# SuperTiny-REV4.net
KiCad netlist of a schematic drawn in EAGLE
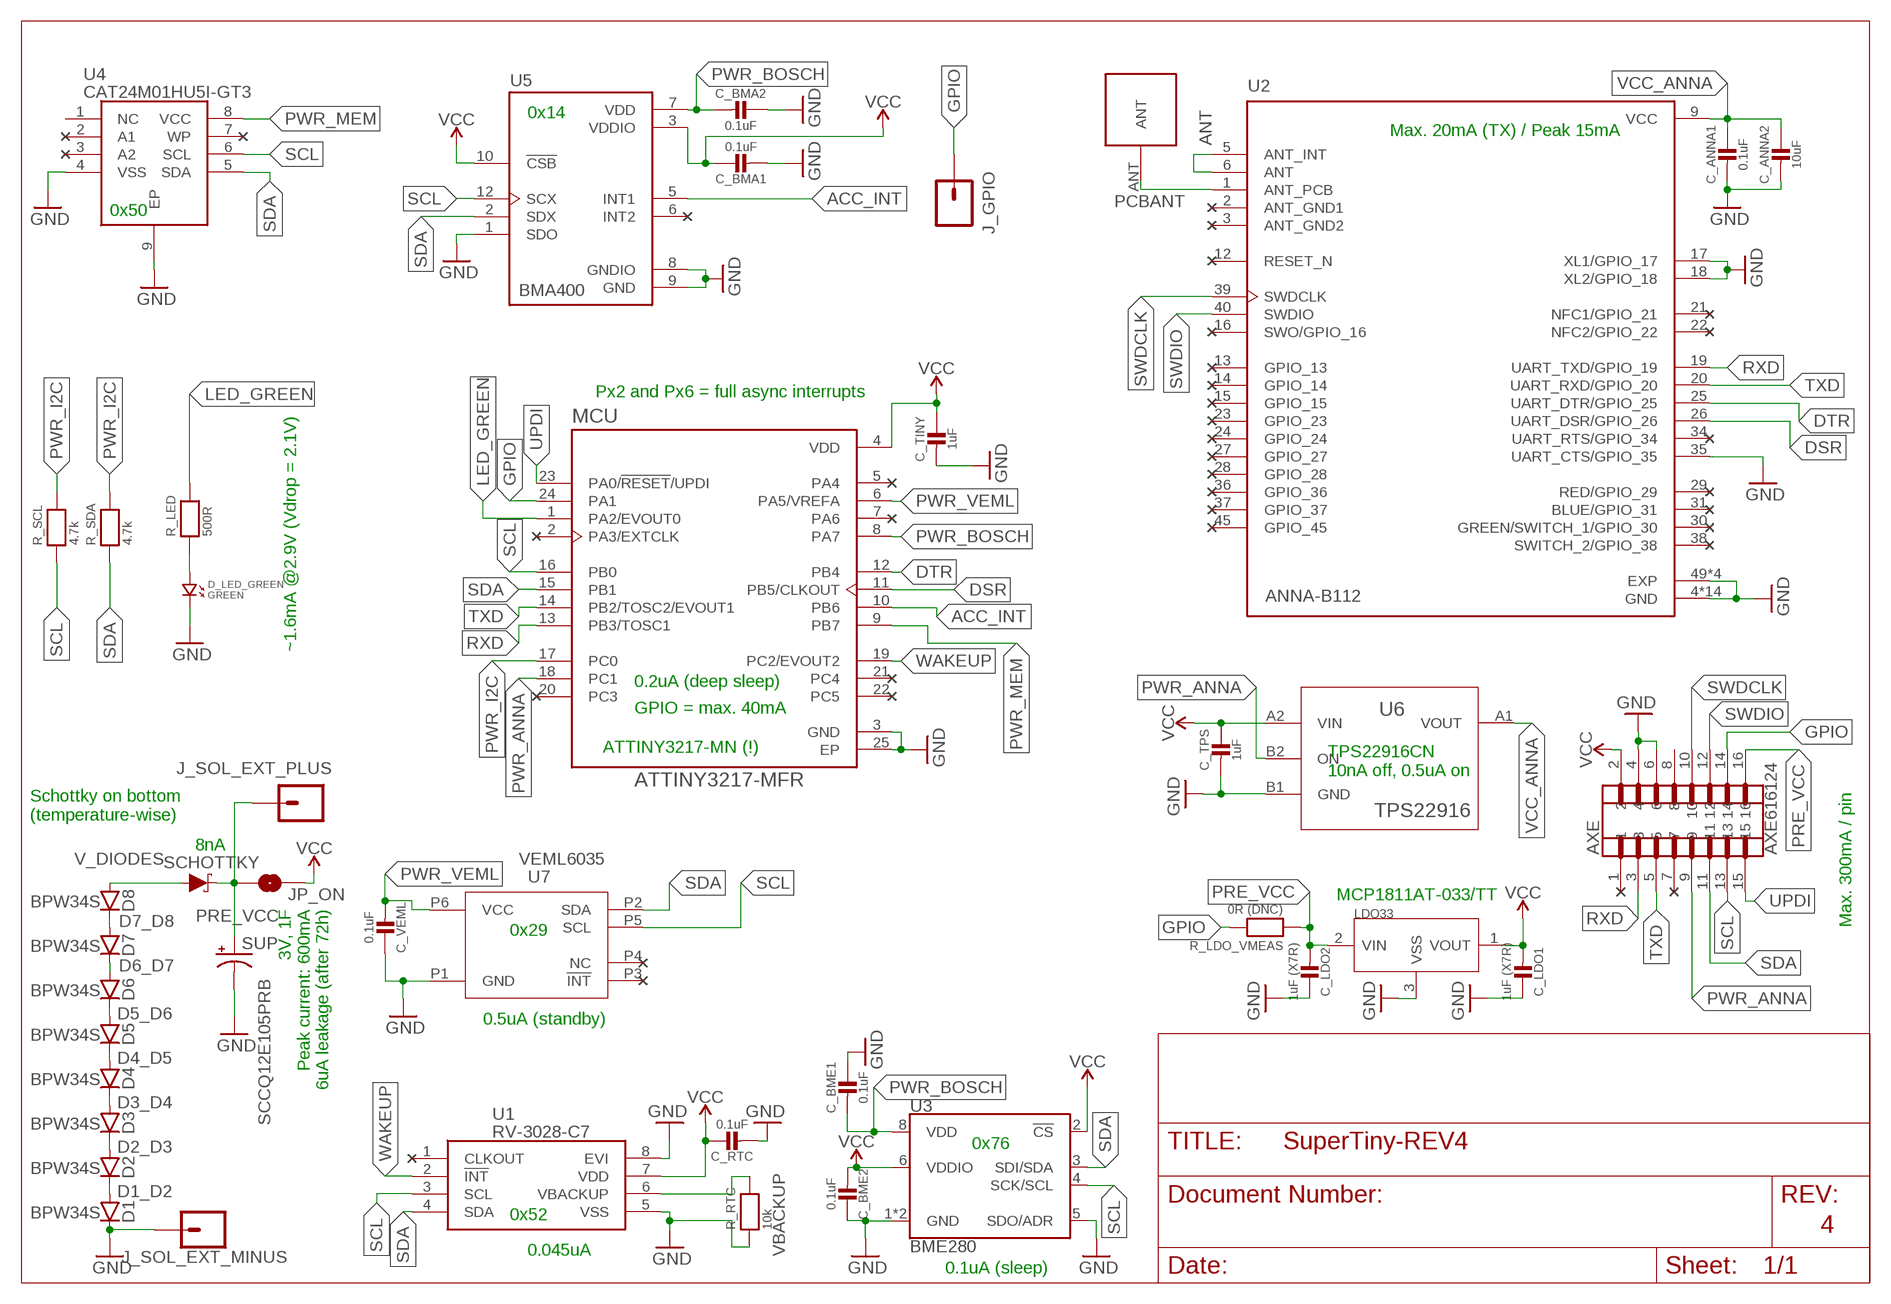
[diagram p0: schematic, sheet 1]

(export (version "E")
  (design (tool "Eeschema 10.0.6"))
  (components
    (comp (ref "AXE")
      (value "AXE616124")
      (footprint "eagle-import:AXE616124")
      (libsource (lib "eagle-import") (part "AXE616124"))
    )
    (comp (ref "C_ANNA1")
      (value "0.1uF")
      (footprint "eagle-import:MICROBUILDER__0402MP")
      (libsource (lib "eagle-import") (part "MICROBUILDER_CAP_CERAMIC_0402MP"))
    )
    (comp (ref "C_ANNA2")
      (value "10uF")
      (footprint "eagle-import:MICROBUILDER__0402MP")
      (libsource (lib "eagle-import") (part "MICROBUILDER_CAP_CERAMIC_0402MP"))
    )
    (comp (ref "C_BMA1")
      (value "0.1uF")
      (footprint "eagle-import:MICROBUILDER__0402MP")
      (fields (field (name "SPICEPREFIX") "C"))
      (libsource (lib "eagle-import") (part "MICROBUILDER_CAP_CERAMIC_0402MP"))
    )
    (comp (ref "C_BMA2")
      (value "0.1uF")
      (footprint "eagle-import:MICROBUILDER__0402MP")
      (fields (field (name "SPICEPREFIX") "C"))
      (libsource (lib "eagle-import") (part "MICROBUILDER_CAP_CERAMIC_0402MP"))
    )
    (comp (ref "C_BME1")
      (value "0.1uF")
      (footprint "eagle-import:MICROBUILDER__0402MP")
      (libsource (lib "eagle-import") (part "MICROBUILDER_CAP_CERAMIC_0402MP"))
    )
    (comp (ref "C_BME2")
      (value "0.1uF")
      (footprint "eagle-import:MICROBUILDER__0402MP")
      (libsource (lib "eagle-import") (part "MICROBUILDER_CAP_CERAMIC_0402MP"))
    )
    (comp (ref "C_LDO1")
      (value "1uF (X7R)")
      (footprint "eagle-import:MICROBUILDER__0402MP")
      (libsource (lib "eagle-import") (part "MICROBUILDER_CAP_CERAMIC_0402MP"))
    )
    (comp (ref "C_LDO2")
      (value "1uF (X7R)")
      (footprint "eagle-import:MICROBUILDER__0402MP")
      (libsource (lib "eagle-import") (part "MICROBUILDER_CAP_CERAMIC_0402MP"))
    )
    (comp (ref "C_RTC")
      (value "0.1uF")
      (footprint "eagle-import:MICROBUILDER__0402MP")
      (fields (field (name "SPICEPREFIX") "C"))
      (libsource (lib "eagle-import") (part "MICROBUILDER_CAP_CERAMIC_0402MP"))
    )
    (comp (ref "C_TINY")
      (value "1uF")
      (footprint "eagle-import:MICROBUILDER__0402MP")
      (libsource (lib "eagle-import") (part "MICROBUILDER_CAP_CERAMIC_0402MP"))
    )
    (comp (ref "C_TPS")
      (value "1uF")
      (footprint "eagle-import:MICROBUILDER__0402MP")
      (libsource (lib "eagle-import") (part "MICROBUILDER_CAP_CERAMIC_0402MP"))
    )
    (comp (ref "C_VEML")
      (value "0.1uF")
      (footprint "eagle-import:MICROBUILDER__0402MP")
      (libsource (lib "eagle-import") (part "MICROBUILDER_CAP_CERAMIC_0402MP"))
    )
    (comp (ref "D1")
      (value "BPW34S")
      (footprint "eagle-import:BPW34S")
      (libsource (lib "eagle-import") (part "BPW34S"))
    )
    (comp (ref "D2")
      (value "BPW34S")
      (footprint "eagle-import:BPW34S")
      (libsource (lib "eagle-import") (part "BPW34S"))
    )
    (comp (ref "D3")
      (value "BPW34S")
      (footprint "eagle-import:BPW34S")
      (libsource (lib "eagle-import") (part "BPW34S"))
    )
    (comp (ref "D4")
      (value "BPW34S")
      (footprint "eagle-import:BPW34S")
      (libsource (lib "eagle-import") (part "BPW34S"))
    )
    (comp (ref "D5")
      (value "BPW34S")
      (footprint "eagle-import:BPW34S")
      (libsource (lib "eagle-import") (part "BPW34S"))
    )
    (comp (ref "D6")
      (value "BPW34S")
      (footprint "eagle-import:BPW34S")
      (libsource (lib "eagle-import") (part "BPW34S"))
    )
    (comp (ref "D7")
      (value "BPW34S")
      (footprint "eagle-import:BPW34S")
      (libsource (lib "eagle-import") (part "BPW34S"))
    )
    (comp (ref "D8")
      (value "BPW34S")
      (footprint "eagle-import:BPW34S")
      (libsource (lib "eagle-import") (part "BPW34S"))
    )
    (comp (ref "D_LED_GREEN")
      (value "GREEN")
      (footprint "eagle-import:CMONR_STANDARDPARTS_0402.LED")
      (libsource (lib "eagle-import") (part "CMONR_STANDARDPARTS_LED.0402"))
    )
    (comp (ref "JP_ON")
      (value "JUMPER-SMT_2_NO_NO-SILK")
      (footprint "eagle-import:SMT-JUMPER_2_NO_NO-SILK")
      (libsource (lib "eagle-import") (part "JUMPER-SMT_2_NO_NO-SILK"))
    )
    (comp (ref "J_GPIO")
      (value "CONN_01PTH_NO_SILK_SMALL")
      (footprint "eagle-import:1X01_SMALL")
      (libsource (lib "eagle-import") (part "CONN_01PTH_NO_SILK_SMALL"))
    )
    (comp (ref "J_SOL_EXT_MINUS")
      (value "CONN_01PTH_NO_SILK_SMALL")
      (footprint "eagle-import:1X01_SMALL")
      (libsource (lib "eagle-import") (part "CONN_01PTH_NO_SILK_SMALL"))
    )
    (comp (ref "J_SOL_EXT_PLUS")
      (value "CONN_01PTH_NO_SILK_SMALL")
      (footprint "eagle-import:1X01_SMALL")
      (libsource (lib "eagle-import") (part "CONN_01PTH_NO_SILK_SMALL"))
    )
    (comp (ref "LDO33")
      (value "MCP1812BT-018LB")
      (footprint "eagle-import:SOT-23")
      (fields (field (name "MF") "Torex") (field (name "MP") "XC6206P332MR-G"))
      (libsource (lib "eagle-import") (part "MCP1812BT-018LB"))
    )
    (comp (ref "MCU")
      (value "ATTINY3217-MFR")
      (footprint "eagle-import:QFN50P400X400X90-25N")
      (fields (field (name "MF") "Microchip"))
      (libsource (lib "eagle-import") (part "ATTINY3217-MFR"))
    )
    (comp (ref "R_LDO_VMEAS")
      (value "0R (DNC)")
      (footprint "eagle-import:MICROBUILDER__0402MP")
      (libsource (lib "eagle-import") (part "MICROBUILDER_RESISTOR_0402MP"))
    )
    (comp (ref "R_LED")
      (value "500R")
      (footprint "eagle-import:MICROBUILDER__0402MP")
      (libsource (lib "eagle-import") (part "MICROBUILDER_RESISTOR_0402MP"))
    )
    (comp (ref "R_RTC")
      (value "10k")
      (footprint "eagle-import:MICROBUILDER__0402MP")
      (libsource (lib "eagle-import") (part "MICROBUILDER_RESISTOR_0402MP"))
    )
    (comp (ref "R_SCL")
      (value "4.7k")
      (footprint "eagle-import:MICROBUILDER__0402MP")
      (libsource (lib "eagle-import") (part "MICROBUILDER_RESISTOR_0402MP"))
    )
    (comp (ref "R_SDA")
      (value "4.7k")
      (footprint "eagle-import:MICROBUILDER__0402MP")
      (libsource (lib "eagle-import") (part "MICROBUILDER_RESISTOR_0402MP"))
    )
    (comp (ref "SCHOTTKY")
      (value "NSR0140P2T5G")
      (footprint "eagle-import:NSR0140P2T5G")
      (libsource (lib "eagle-import") (part "NSR0140P2T5G"))
    )
    (comp (ref "SUP")
      (value "SCCQ12E105PRB")
      (footprint "eagle-import:SCCQ12E105PRB")
      (libsource (lib "eagle-import") (part "SCCQ12E105PRB"))
    )
    (comp (ref "U$4")
      (value "ANNA-B112-PCB-ANTENNA")
      (footprint "eagle-import:ANNA-B112-PCB-ANTENNA")
      (libsource (lib "eagle-import") (part "ANNA-B112-PCB-ANTENNA"))
    )
    (comp (ref "U1")
      (value "RV-3028-C7")
      (footprint "eagle-import:RV3028C7")
      (fields (field (name "SPICEPREFIX") "X"))
      (libsource (lib "eagle-import") (part "RV-3028-C7"))
    )
    (comp (ref "U2")
      (value "ANNA-B112")
      (footprint "eagle-import:XCVR_ANNA-B112")
      (fields (field (name "MF") "U-Blox America"))
      (libsource (lib "eagle-import") (part "ANNA-B112"))
    )
    (comp (ref "U3")
      (value "BME280")
      (footprint "eagle-import:LGA-8-2.5X2.5")
      (libsource (lib "eagle-import") (part "BME280"))
    )
    (comp (ref "U4")
      (value "CAT24M01HU5I-GT3")
      (footprint "eagle-import:SON50P300X200X55-9N")
      (fields
        (field (name "MOUSER_PART_NUMBER") "863-CAT24M01HU5I-GT3")
        (field (name "RS_PART_NUMBER") "7814831P")
      )
      (libsource (lib "eagle-import") (part "CAT24M01HU5I-GT3"))
    )
    (comp (ref "U5")
      (value "BMA400")
      (footprint "eagle-import:XDCR_BMA400")
      (fields (field (name "MF") "Bosch Sensortec"))
      (libsource (lib "eagle-import") (part "BMA400"))
    )
    (comp (ref "U6")
      (value "TPS22916")
      (footprint "eagle-import:TPS22916")
      (fields (field (name "MF") "Texas Instruments") (field (name "MP") "LP5900TL-3.0"))
      (libsource (lib "eagle-import") (part "TPS22916"))
    )
    (comp (ref "U7")
      (value "VEML6035")
      (footprint "eagle-import:VEML6035")
      (libsource (lib "eagle-import") (part "VEML6035"))
    )
  )
  (nets
    (net (code "1") (name "/ANT") (class "Default")
      (node (ref "U2") (pin "5") (pinfunction "ANT_INT_5") (pintype "input"))
      (node (ref "U2") (pin "6") (pinfunction "ANT_6") (pintype "bidirectional"))
    )
    (net (code "2") (name "/ANT_GND1") (class "Default")
      (node (ref "U2") (pin "2") (pinfunction "ANT_GND1_2") (pintype "power_in"))
    )
    (net (code "3") (name "/ANT_GND2") (class "Default")
      (node (ref "U2") (pin "3") (pinfunction "ANT_GND2_3") (pintype "power_in"))
    )
    (net (code "4") (name "/D1_D2") (class "Default")
      (node (ref "D1") (pin "PLUS") (pinfunction "PLUS_PLUS") (pintype "passive"))
      (node (ref "D2") (pin "MINUS") (pinfunction "MINUS_MINUS") (pintype "passive"))
    )
    (net (code "5") (name "/D2_D3") (class "Default")
      (node (ref "D2") (pin "PLUS") (pinfunction "PLUS_PLUS") (pintype "passive"))
      (node (ref "D3") (pin "MINUS") (pinfunction "MINUS_MINUS") (pintype "passive"))
    )
    (net (code "6") (name "/D3_D4") (class "Default")
      (node (ref "D3") (pin "PLUS") (pinfunction "PLUS_PLUS") (pintype "passive"))
      (node (ref "D4") (pin "MINUS") (pinfunction "MINUS_MINUS") (pintype "passive"))
    )
    (net (code "7") (name "/D4_D5") (class "Default")
      (node (ref "D4") (pin "PLUS") (pinfunction "PLUS_PLUS") (pintype "passive"))
      (node (ref "D5") (pin "MINUS") (pinfunction "MINUS_MINUS") (pintype "passive"))
    )
    (net (code "8") (name "/D5_D6") (class "Default")
      (node (ref "D5") (pin "PLUS") (pinfunction "PLUS_PLUS") (pintype "passive"))
      (node (ref "D6") (pin "MINUS") (pinfunction "MINUS_MINUS") (pintype "passive"))
    )
    (net (code "9") (name "/D6_D7") (class "Default")
      (node (ref "D6") (pin "PLUS") (pinfunction "PLUS_PLUS") (pintype "passive"))
      (node (ref "D7") (pin "MINUS") (pinfunction "MINUS_MINUS") (pintype "passive"))
    )
    (net (code "10") (name "/D7_D8") (class "Default")
      (node (ref "D7") (pin "PLUS") (pinfunction "PLUS_PLUS") (pintype "passive"))
      (node (ref "D8") (pin "MINUS") (pinfunction "MINUS_MINUS") (pintype "passive"))
    )
    (net (code "11") (name "/PCBANT") (class "Default")
      (node (ref "U$4") (pin "ANT") (pinfunction "ANT_ANT") (pintype "bidirectional"))
      (node (ref "U2") (pin "1") (pinfunction "ANT_PCB_1") (pintype "power_in"))
    )
    (net (code "12") (name "/VBACKUP") (class "Default")
      (node (ref "R_RTC") (pin "2") (pinfunction "2_2") (pintype "passive"))
      (node (ref "U1") (pin "6") (pinfunction "VBACKUP_6") (pintype "bidirectional"))
    )
    (net (code "13") (name "/V_DIODES") (class "Default")
      (node (ref "D8") (pin "PLUS") (pinfunction "PLUS_PLUS") (pintype "passive"))
      (node (ref "SCHOTTKY") (pin "P$1") (pinfunction "AN_P$1") (pintype "passive"))
    )
    (net (code "14") (name "ACC_INT") (class "Default")
      (node (ref "MCU") (pin "10") (pinfunction "PB6_10") (pintype "bidirectional"))
      (node (ref "U5") (pin "5") (pinfunction "INT1_5") (pintype "bidirectional"))
    )
    (net (code "15") (name "DSR") (class "Default")
      (node (ref "MCU") (pin "11") (pinfunction "PB5/CLKOUT_11") (pintype "bidirectional"))
      (node (ref "U2") (pin "26") (pinfunction "UART_DSR/GPIO_26_26") (pintype "bidirectional"))
    )
    (net (code "16") (name "DTR") (class "Default")
      (node (ref "MCU") (pin "12") (pinfunction "PB4_12") (pintype "bidirectional"))
      (node (ref "U2") (pin "25") (pinfunction "UART_DTR/GPIO_25_25") (pintype "bidirectional"))
    )
    (net (code "17") (name "GND") (class "Default")
      (node (ref "AXE") (pin "4") (pinfunction "4_4") (pintype "passive"))
      (node (ref "AXE") (pin "6") (pinfunction "6_6") (pintype "passive"))
      (node (ref "C_ANNA1") (pin "2") (pinfunction "2_2") (pintype "passive"))
      (node (ref "C_ANNA2") (pin "2") (pinfunction "2_2") (pintype "passive"))
      (node (ref "C_BMA1") (pin "2") (pinfunction "2_2") (pintype "passive"))
      (node (ref "C_BMA2") (pin "1") (pinfunction "1_1") (pintype "passive"))
      (node (ref "C_BME1") (pin "1") (pinfunction "1_1") (pintype "passive"))
      (node (ref "C_BME2") (pin "1") (pinfunction "1_1") (pintype "passive"))
      (node (ref "C_LDO1") (pin "1") (pinfunction "1_1") (pintype "passive"))
      (node (ref "C_LDO2") (pin "1") (pinfunction "1_1") (pintype "passive"))
      (node (ref "C_RTC") (pin "2") (pinfunction "2_2") (pintype "passive"))
      (node (ref "C_TINY") (pin "2") (pinfunction "2_2") (pintype "passive"))
      (node (ref "C_TPS") (pin "2") (pinfunction "2_2") (pintype "passive"))
      (node (ref "C_VEML") (pin "1") (pinfunction "1_1") (pintype "passive"))
      (node (ref "D1") (pin "MINUS") (pinfunction "MINUS_MINUS") (pintype "passive"))
      (node (ref "D_LED_GREEN") (pin "P$2") (pinfunction "2_P$2") (pintype "bidirectional"))
      (node (ref "J_SOL_EXT_MINUS") (pin "P$1") (pinfunction "1_P$1") (pintype "passive"))
      (node (ref "LDO33") (pin "3") (pinfunction "VSS_3") (pintype "power_in"))
      (node (ref "MCU") (pin "25") (pinfunction "EP_25") (pintype "power_in"))
      (node (ref "MCU") (pin "3") (pinfunction "GND_3") (pintype "power_in"))
      (node (ref "R_RTC") (pin "1") (pinfunction "1_1") (pintype "passive"))
      (node (ref "SUP") (pin "MINUS") (pinfunction "-_MINUS") (pintype "passive"))
      (node (ref "U1") (pin "5") (pinfunction "VSS_5") (pintype "bidirectional"))
      (node (ref "U1") (pin "8") (pinfunction "EVI_8") (pintype "bidirectional"))
      (node (ref "U2") (pin "10") (pinfunction "GND_10") (pintype "power_in"))
      (node (ref "U2") (pin "11") (pinfunction "GND_11") (pintype "power_in"))
      (node (ref "U2") (pin "17") (pinfunction "XL1/GPIO_17_17") (pintype "bidirectional"))
      (node (ref "U2") (pin "18") (pinfunction "XL2/GPIO_18_18") (pintype "bidirectional"))
      (node (ref "U2") (pin "32") (pinfunction "GND_32") (pintype "power_in"))
      (node (ref "U2") (pin "33") (pinfunction "GND_33") (pintype "power_in"))
      (node (ref "U2") (pin "35") (pinfunction "UART_CTS/GPIO_35_35") (pintype "bidirectional"))
      (node (ref "U2") (pin "4") (pinfunction "GND_4") (pintype "power_in"))
      (node (ref "U2") (pin "41") (pinfunction "GND_41") (pintype "power_in"))
      (node (ref "U2") (pin "42") (pinfunction "GND_42") (pintype "power_in"))
      (node (ref "U2") (pin "43") (pinfunction "GND_43") (pintype "power_in"))
      (node (ref "U2") (pin "44") (pinfunction "GND_44") (pintype "power_in"))
      (node (ref "U2") (pin "46") (pinfunction "GND_46") (pintype "power_in"))
      (node (ref "U2") (pin "47") (pinfunction "GND_47") (pintype "power_in"))
      (node (ref "U2") (pin "48") (pinfunction "GND_48") (pintype "power_in"))
      (node (ref "U2") (pin "49") (pinfunction "EXP_49") (pintype "power_in"))
      (node (ref "U2") (pin "50") (pinfunction "EXP_50") (pintype "power_in"))
      (node (ref "U2") (pin "51") (pinfunction "EXP_51") (pintype "power_in"))
      (node (ref "U2") (pin "52") (pinfunction "EXP_52") (pintype "power_in"))
      (node (ref "U2") (pin "7") (pinfunction "GND_7") (pintype "power_in"))
      (node (ref "U2") (pin "8") (pinfunction "GND_8") (pintype "power_in"))
      (node (ref "U3") (pin "1") (pinfunction "GND_1") (pintype "bidirectional"))
      (node (ref "U3") (pin "5") (pinfunction "SDO/ADR_5") (pintype "bidirectional"))
      (node (ref "U3") (pin "7") (pinfunction "GND_7") (pintype "bidirectional"))
      (node (ref "U4") (pin "4") (pinfunction "VSS_4") (pintype "power_in"))
      (node (ref "U4") (pin "9") (pinfunction "EP_9") (pintype "bidirectional"))
      (node (ref "U5") (pin "1") (pinfunction "SDO_1") (pintype "bidirectional"))
      (node (ref "U5") (pin "8") (pinfunction "GNDIO_8") (pintype "power_in"))
      (node (ref "U5") (pin "9") (pinfunction "GND_9") (pintype "power_in"))
      (node (ref "U6") (pin "B1") (pinfunction "GND_B1") (pintype "passive"))
      (node (ref "U7") (pin "P1") (pinfunction "GND_P1") (pintype "power_in"))
    )
    (net (code "18") (name "GPIO") (class "Default")
      (node (ref "AXE") (pin "14") (pinfunction "14_14") (pintype "passive"))
      (node (ref "J_GPIO") (pin "P$1") (pinfunction "1_P$1") (pintype "passive"))
      (node (ref "MCU") (pin "24") (pinfunction "PA1_24") (pintype "bidirectional"))
      (node (ref "R_LDO_VMEAS") (pin "2") (pinfunction "2_2") (pintype "passive"))
    )
    (net (code "19") (name "LED_GREEN") (class "Default")
      (node (ref "MCU") (pin "1") (pinfunction "PA2/EVOUT0_1") (pintype "bidirectional"))
      (node (ref "R_LED") (pin "2") (pinfunction "2_2") (pintype "passive"))
    )
    (net (code "20") (name "Net-(D_LED_GREEN-1)") (class "Default")
      (node (ref "D_LED_GREEN") (pin "P$1") (pinfunction "1_P$1") (pintype "bidirectional"))
      (node (ref "R_LED") (pin "1") (pinfunction "1_1") (pintype "passive"))
    )
    (net (code "21") (name "PRE_VCC") (class "Default")
      (node (ref "AXE") (pin "16") (pinfunction "16_16") (pintype "passive"))
      (node (ref "C_LDO2") (pin "2") (pinfunction "2_2") (pintype "passive"))
      (node (ref "JP_ON") (pin "1") (pinfunction "1_1") (pintype "passive"))
      (node (ref "J_SOL_EXT_PLUS") (pin "P$1") (pinfunction "1_P$1") (pintype "passive"))
      (node (ref "LDO33") (pin "2") (pinfunction "VIN_2") (pintype "input"))
      (node (ref "R_LDO_VMEAS") (pin "1") (pinfunction "1_1") (pintype "passive"))
      (node (ref "SCHOTTKY") (pin "P$2") (pinfunction "CA_P$2") (pintype "passive"))
      (node (ref "SUP") (pin "PLUS") (pinfunction "+_PLUS") (pintype "passive"))
    )
    (net (code "22") (name "PWR_ANNA") (class "Default")
      (node (ref "AXE") (pin "9") (pinfunction "9_9") (pintype "passive"))
      (node (ref "MCU") (pin "18") (pinfunction "PC1_18") (pintype "bidirectional"))
      (node (ref "U6") (pin "B2") (pinfunction "ON_B2") (pintype "input"))
    )
    (net (code "23") (name "PWR_BOSCH") (class "Default")
      (node (ref "C_BMA2") (pin "2") (pinfunction "2_2") (pintype "passive"))
      (node (ref "C_BME1") (pin "2") (pinfunction "2_2") (pintype "passive"))
      (node (ref "MCU") (pin "8") (pinfunction "PA7_8") (pintype "bidirectional"))
      (node (ref "U3") (pin "8") (pinfunction "VDD_8") (pintype "bidirectional"))
      (node (ref "U5") (pin "7") (pinfunction "VDD_7") (pintype "power_in"))
    )
    (net (code "24") (name "PWR_I2C") (class "Default")
      (node (ref "MCU") (pin "17") (pinfunction "PC0_17") (pintype "bidirectional"))
      (node (ref "R_SCL") (pin "2") (pinfunction "2_2") (pintype "passive"))
      (node (ref "R_SDA") (pin "2") (pinfunction "2_2") (pintype "passive"))
    )
    (net (code "25") (name "PWR_MEM") (class "Default")
      (node (ref "MCU") (pin "9") (pinfunction "PB7_9") (pintype "bidirectional"))
      (node (ref "U4") (pin "8") (pinfunction "VCC_8") (pintype "power_in"))
    )
    (net (code "26") (name "PWR_VEML") (class "Default")
      (node (ref "C_VEML") (pin "2") (pinfunction "2_2") (pintype "passive"))
      (node (ref "MCU") (pin "6") (pinfunction "PA5/VREFA_6") (pintype "bidirectional"))
      (node (ref "U7") (pin "P6") (pinfunction "VCC_P6") (pintype "power_in"))
    )
    (net (code "27") (name "RXD") (class "Default")
      (node (ref "AXE") (pin "3") (pinfunction "3_3") (pintype "passive"))
      (node (ref "MCU") (pin "13") (pinfunction "PB3/TOSC1_13") (pintype "bidirectional"))
      (node (ref "U2") (pin "19") (pinfunction "UART_TXD/GPIO_19_19") (pintype "bidirectional"))
    )
    (net (code "28") (name "SCL") (class "Default")
      (node (ref "AXE") (pin "13") (pinfunction "13_13") (pintype "passive"))
      (node (ref "MCU") (pin "16") (pinfunction "PB0_16") (pintype "bidirectional"))
      (node (ref "R_SCL") (pin "1") (pinfunction "1_1") (pintype "passive"))
      (node (ref "U1") (pin "3") (pinfunction "SCL_3") (pintype "bidirectional"))
      (node (ref "U3") (pin "4") (pinfunction "SCK/SCL_4") (pintype "bidirectional"))
      (node (ref "U4") (pin "6") (pinfunction "SCL_6") (pintype "bidirectional"))
      (node (ref "U5") (pin "12") (pinfunction "SCX_12") (pintype "input"))
      (node (ref "U7") (pin "P5") (pinfunction "SCL_P5") (pintype "bidirectional"))
    )
    (net (code "29") (name "SDA") (class "Default")
      (node (ref "AXE") (pin "11") (pinfunction "11_11") (pintype "passive"))
      (node (ref "MCU") (pin "15") (pinfunction "PB1_15") (pintype "bidirectional"))
      (node (ref "R_SDA") (pin "1") (pinfunction "1_1") (pintype "passive"))
      (node (ref "U1") (pin "4") (pinfunction "SDA_4") (pintype "bidirectional"))
      (node (ref "U3") (pin "3") (pinfunction "SDI/SDA_3") (pintype "bidirectional"))
      (node (ref "U4") (pin "5") (pinfunction "SDA_5") (pintype "bidirectional"))
      (node (ref "U5") (pin "2") (pinfunction "SDX_2") (pintype "bidirectional"))
      (node (ref "U7") (pin "P2") (pinfunction "SDA_P2") (pintype "bidirectional"))
    )
    (net (code "30") (name "SWDCLK") (class "Default")
      (node (ref "AXE") (pin "10") (pinfunction "10_10") (pintype "passive"))
      (node (ref "U2") (pin "39") (pinfunction "SWDCLK_39") (pintype "input"))
    )
    (net (code "31") (name "SWDIO") (class "Default")
      (node (ref "AXE") (pin "12") (pinfunction "12_12") (pintype "passive"))
      (node (ref "U2") (pin "40") (pinfunction "SWDIO_40") (pintype "bidirectional"))
    )
    (net (code "32") (name "TXD") (class "Default")
      (node (ref "AXE") (pin "5") (pinfunction "5_5") (pintype "passive"))
      (node (ref "MCU") (pin "14") (pinfunction "PB2/TOSC2/EVOUT1_14") (pintype "bidirectional"))
      (node (ref "U2") (pin "20") (pinfunction "UART_RXD/GPIO_20_20") (pintype "bidirectional"))
    )
    (net (code "33") (name "UPDI") (class "Default")
      (node (ref "AXE") (pin "15") (pinfunction "15_15") (pintype "passive"))
      (node (ref "MCU") (pin "23") (pinfunction "PA0/~{RESET}/UPDI_23") (pintype "bidirectional"))
    )
    (net (code "34") (name "VCC") (class "Default")
      (node (ref "AXE") (pin "2") (pinfunction "2_2") (pintype "passive"))
      (node (ref "C_BMA1") (pin "1") (pinfunction "1_1") (pintype "passive"))
      (node (ref "C_BME2") (pin "2") (pinfunction "2_2") (pintype "passive"))
      (node (ref "C_LDO1") (pin "2") (pinfunction "2_2") (pintype "passive"))
      (node (ref "C_RTC") (pin "1") (pinfunction "1_1") (pintype "passive"))
      (node (ref "C_TINY") (pin "1") (pinfunction "1_1") (pintype "passive"))
      (node (ref "C_TPS") (pin "1") (pinfunction "1_1") (pintype "passive"))
      (node (ref "JP_ON") (pin "2") (pinfunction "2_2") (pintype "passive"))
      (node (ref "LDO33") (pin "1") (pinfunction "VOUT_1") (pintype "output"))
      (node (ref "MCU") (pin "4") (pinfunction "VDD_4") (pintype "power_in"))
      (node (ref "U1") (pin "7") (pinfunction "VDD_7") (pintype "bidirectional"))
      (node (ref "U3") (pin "2") (pinfunction "~{CS}_2") (pintype "bidirectional"))
      (node (ref "U3") (pin "6") (pinfunction "VDDIO_6") (pintype "bidirectional"))
      (node (ref "U5") (pin "10") (pinfunction "~{CSB}_10") (pintype "input"))
      (node (ref "U5") (pin "3") (pinfunction "VDDIO_3") (pintype "power_in"))
      (node (ref "U6") (pin "A2") (pinfunction "VIN_A2") (pintype "power_in"))
    )
    (net (code "35") (name "VCC_ANNA") (class "Default")
      (node (ref "C_ANNA1") (pin "1") (pinfunction "1_1") (pintype "passive"))
      (node (ref "C_ANNA2") (pin "1") (pinfunction "1_1") (pintype "passive"))
      (node (ref "U2") (pin "9") (pinfunction "VCC_9") (pintype "power_in"))
      (node (ref "U6") (pin "A1") (pinfunction "VOUT_A1") (pintype "output"))
    )
    (net (code "36") (name "WAKEUP") (class "Default")
      (node (ref "MCU") (pin "19") (pinfunction "PC2/EVOUT2_19") (pintype "bidirectional"))
      (node (ref "U1") (pin "2") (pinfunction "~{INT}_2") (pintype "bidirectional"))
    )
    (net (code "37") (name "unconnected-(AXE-Pad1)") (class "Default")
      (node (ref "AXE") (pin "1") (pinfunction "1_1") (pintype "passive"))
    )
    (net (code "38") (name "unconnected-(AXE-Pad7)") (class "Default")
      (node (ref "AXE") (pin "7") (pinfunction "7_7") (pintype "passive"))
    )
    (net (code "39") (name "unconnected-(AXE-Pad8)") (class "Default")
      (node (ref "AXE") (pin "8") (pinfunction "8_8") (pintype "passive"))
    )
    (net (code "40") (name "unconnected-(MCU-PA3{slash}EXTCLK-Pad2)") (class "Default")
      (node (ref "MCU") (pin "2") (pinfunction "PA3/EXTCLK_2") (pintype "bidirectional"))
    )
    (net (code "41") (name "unconnected-(MCU-PA4-Pad5)") (class "Default")
      (node (ref "MCU") (pin "5") (pinfunction "PA4_5") (pintype "bidirectional"))
    )
    (net (code "42") (name "unconnected-(MCU-PA6-Pad7)") (class "Default")
      (node (ref "MCU") (pin "7") (pinfunction "PA6_7") (pintype "bidirectional"))
    )
    (net (code "43") (name "unconnected-(MCU-PC3-Pad20)") (class "Default")
      (node (ref "MCU") (pin "20") (pinfunction "PC3_20") (pintype "bidirectional"))
    )
    (net (code "44") (name "unconnected-(MCU-PC4-Pad21)") (class "Default")
      (node (ref "MCU") (pin "21") (pinfunction "PC4_21") (pintype "bidirectional"))
    )
    (net (code "45") (name "unconnected-(MCU-PC5-Pad22)") (class "Default")
      (node (ref "MCU") (pin "22") (pinfunction "PC5_22") (pintype "bidirectional"))
    )
    (net (code "46") (name "unconnected-(U1-CLKOUT-Pad1)") (class "Default")
      (node (ref "U1") (pin "1") (pinfunction "CLKOUT_1") (pintype "bidirectional"))
    )
    (net (code "47") (name "unconnected-(U2-BLUE{slash}GPIO_31-Pad31)") (class "Default")
      (node (ref "U2") (pin "31") (pinfunction "BLUE/GPIO_31_31") (pintype "bidirectional"))
    )
    (net (code "48") (name "unconnected-(U2-GPIO_13-Pad13)") (class "Default")
      (node (ref "U2") (pin "13") (pinfunction "GPIO_13_13") (pintype "bidirectional"))
    )
    (net (code "49") (name "unconnected-(U2-GPIO_14-Pad14)") (class "Default")
      (node (ref "U2") (pin "14") (pinfunction "GPIO_14_14") (pintype "bidirectional"))
    )
    (net (code "50") (name "unconnected-(U2-GPIO_15-Pad15)") (class "Default")
      (node (ref "U2") (pin "15") (pinfunction "GPIO_15_15") (pintype "bidirectional"))
    )
    (net (code "51") (name "unconnected-(U2-GPIO_23-Pad23)") (class "Default")
      (node (ref "U2") (pin "23") (pinfunction "GPIO_23_23") (pintype "bidirectional"))
    )
    (net (code "52") (name "unconnected-(U2-GPIO_24-Pad24)") (class "Default")
      (node (ref "U2") (pin "24") (pinfunction "GPIO_24_24") (pintype "bidirectional"))
    )
    (net (code "53") (name "unconnected-(U2-GPIO_27-Pad27)") (class "Default")
      (node (ref "U2") (pin "27") (pinfunction "GPIO_27_27") (pintype "bidirectional"))
    )
    (net (code "54") (name "unconnected-(U2-GPIO_28-Pad28)") (class "Default")
      (node (ref "U2") (pin "28") (pinfunction "GPIO_28_28") (pintype "bidirectional"))
    )
    (net (code "55") (name "unconnected-(U2-GPIO_36-Pad36)") (class "Default")
      (node (ref "U2") (pin "36") (pinfunction "GPIO_36_36") (pintype "bidirectional"))
    )
    (net (code "56") (name "unconnected-(U2-GPIO_37-Pad37)") (class "Default")
      (node (ref "U2") (pin "37") (pinfunction "GPIO_37_37") (pintype "bidirectional"))
    )
    (net (code "57") (name "unconnected-(U2-GPIO_45-Pad45)") (class "Default")
      (node (ref "U2") (pin "45") (pinfunction "GPIO_45_45") (pintype "bidirectional"))
    )
    (net (code "58") (name "unconnected-(U2-GREEN{slash}SWITCH_1{slash}GPIO_30-Pad30)") (class "Default")
      (node (ref "U2") (pin "30") (pinfunction "GREEN/SWITCH_1/GPIO_30_30") (pintype "bidirectional"))
    )
    (net (code "59") (name "unconnected-(U2-NFC1{slash}GPIO_21-Pad21)") (class "Default")
      (node (ref "U2") (pin "21") (pinfunction "NFC1/GPIO_21_21") (pintype "bidirectional"))
    )
    (net (code "60") (name "unconnected-(U2-NFC2{slash}GPIO_22-Pad22)") (class "Default")
      (node (ref "U2") (pin "22") (pinfunction "NFC2/GPIO_22_22") (pintype "bidirectional"))
    )
    (net (code "61") (name "unconnected-(U2-RED{slash}GPIO_29-Pad29)") (class "Default")
      (node (ref "U2") (pin "29") (pinfunction "RED/GPIO_29_29") (pintype "bidirectional"))
    )
    (net (code "62") (name "unconnected-(U2-RESET_N-Pad12)") (class "Default")
      (node (ref "U2") (pin "12") (pinfunction "RESET_N_12") (pintype "input"))
    )
    (net (code "63") (name "unconnected-(U2-SWITCH_2{slash}GPIO_38-Pad38)") (class "Default")
      (node (ref "U2") (pin "38") (pinfunction "SWITCH_2/GPIO_38_38") (pintype "bidirectional"))
    )
    (net (code "64") (name "unconnected-(U2-SWO{slash}GPIO_16-Pad16)") (class "Default")
      (node (ref "U2") (pin "16") (pinfunction "SWO/GPIO_16_16") (pintype "bidirectional"))
    )
    (net (code "65") (name "unconnected-(U2-UART_RTS{slash}GPIO_34-Pad34)") (class "Default")
      (node (ref "U2") (pin "34") (pinfunction "UART_RTS/GPIO_34_34") (pintype "bidirectional"))
    )
    (net (code "66") (name "unconnected-(U4-A1-Pad2)") (class "Default")
      (node (ref "U4") (pin "2") (pinfunction "A1_2") (pintype "bidirectional"))
    )
    (net (code "67") (name "unconnected-(U4-A2-Pad3)") (class "Default")
      (node (ref "U4") (pin "3") (pinfunction "A2_3") (pintype "bidirectional"))
    )
    (net (code "68") (name "unconnected-(U4-NC-Pad1)") (class "Default")
      (node (ref "U4") (pin "1") (pinfunction "NC_1") (pintype "no_connect"))
    )
    (net (code "69") (name "unconnected-(U4-WP-Pad7)") (class "Default")
      (node (ref "U4") (pin "7") (pinfunction "WP_7") (pintype "bidirectional"))
    )
    (net (code "70") (name "unconnected-(U5-INT2-Pad6)") (class "Default")
      (node (ref "U5") (pin "6") (pinfunction "INT2_6") (pintype "bidirectional"))
    )
    (net (code "71") (name "unconnected-(U7-NC-PadP4)") (class "Default")
      (node (ref "U7") (pin "P4") (pinfunction "NC_P4") (pintype "bidirectional"))
    )
    (net (code "72") (name "unconnected-(U7-~{INT}-PadP3)") (class "Default")
      (node (ref "U7") (pin "P3") (pinfunction "~{INT}_P3") (pintype "output"))
    )
  )
)
